# net-stepper2.net
KiCad netlist of a schematic drawn in EAGLE
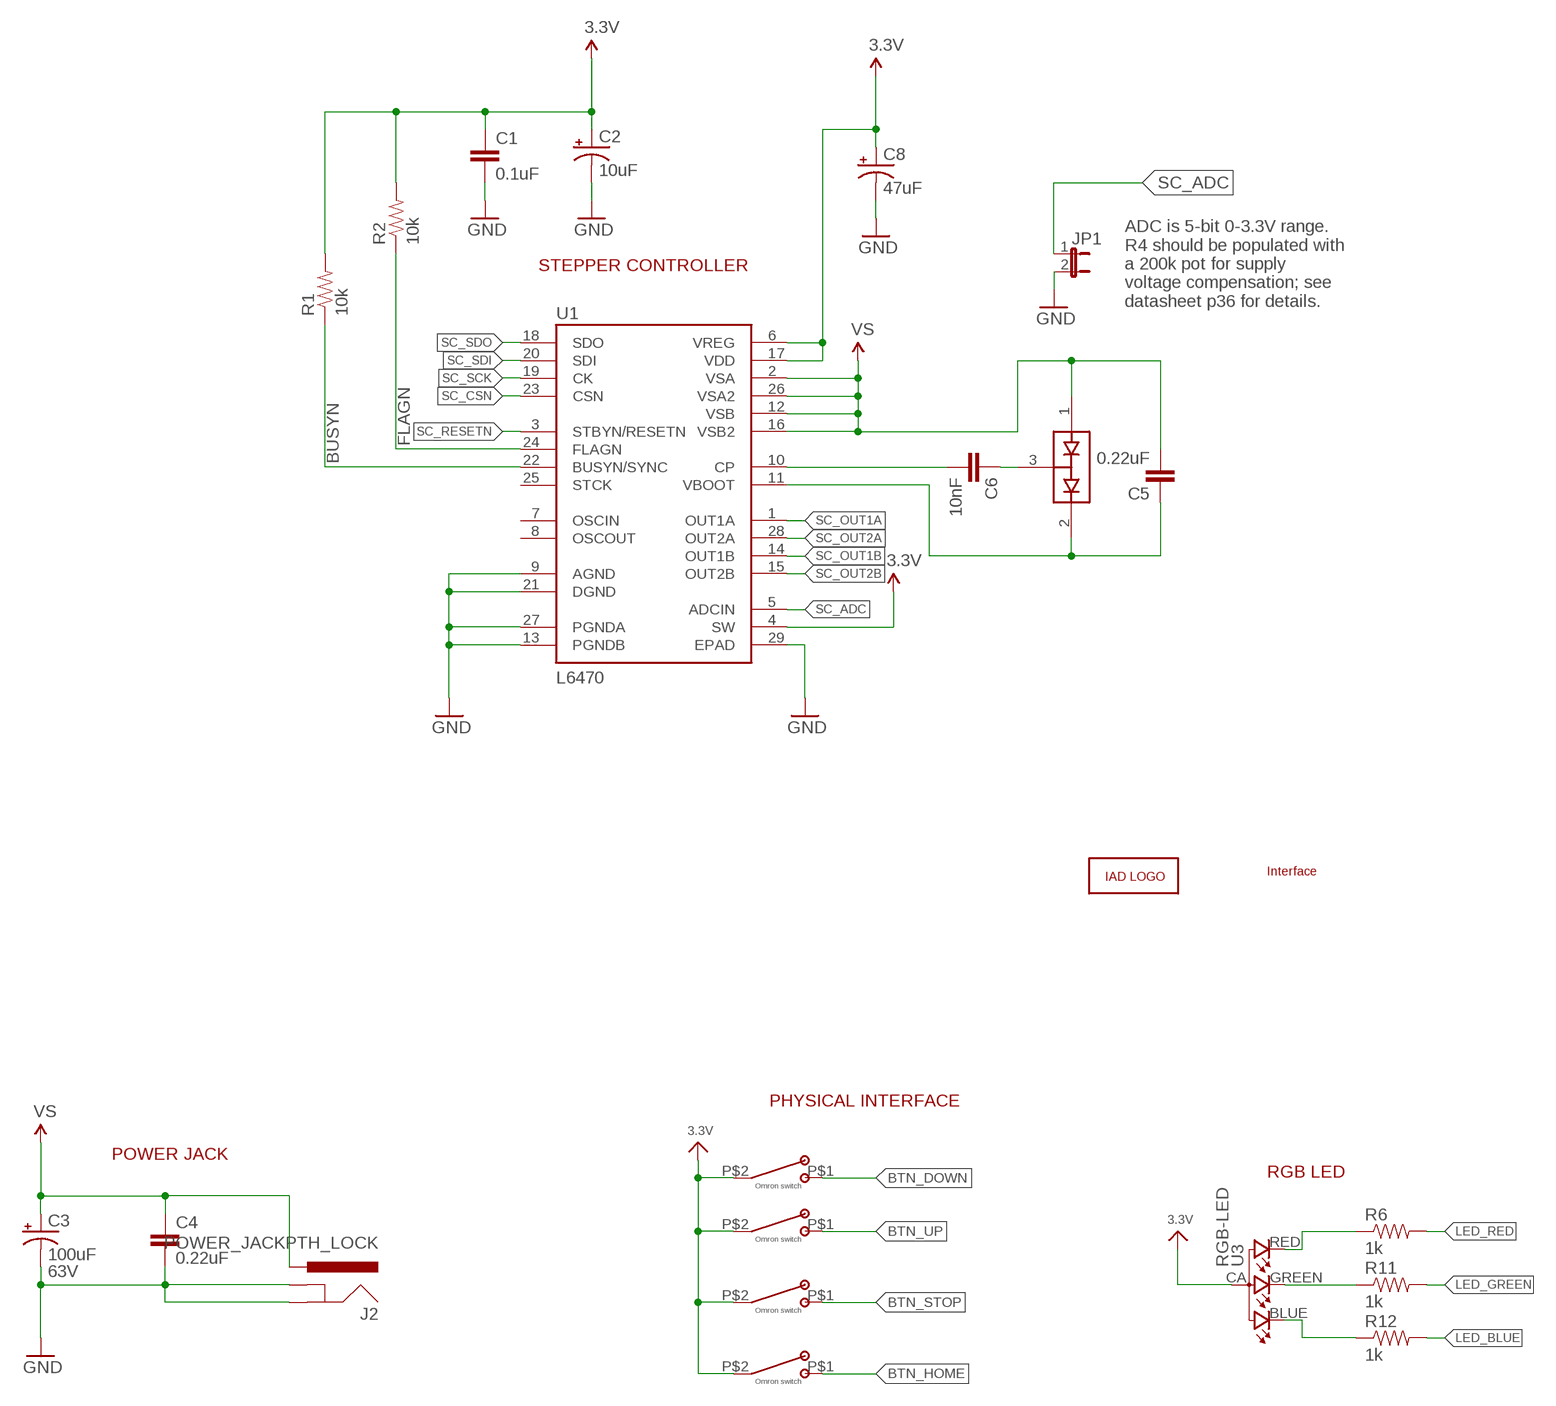
[diagram p0: schematic, sheet 1, part 1 of 2]
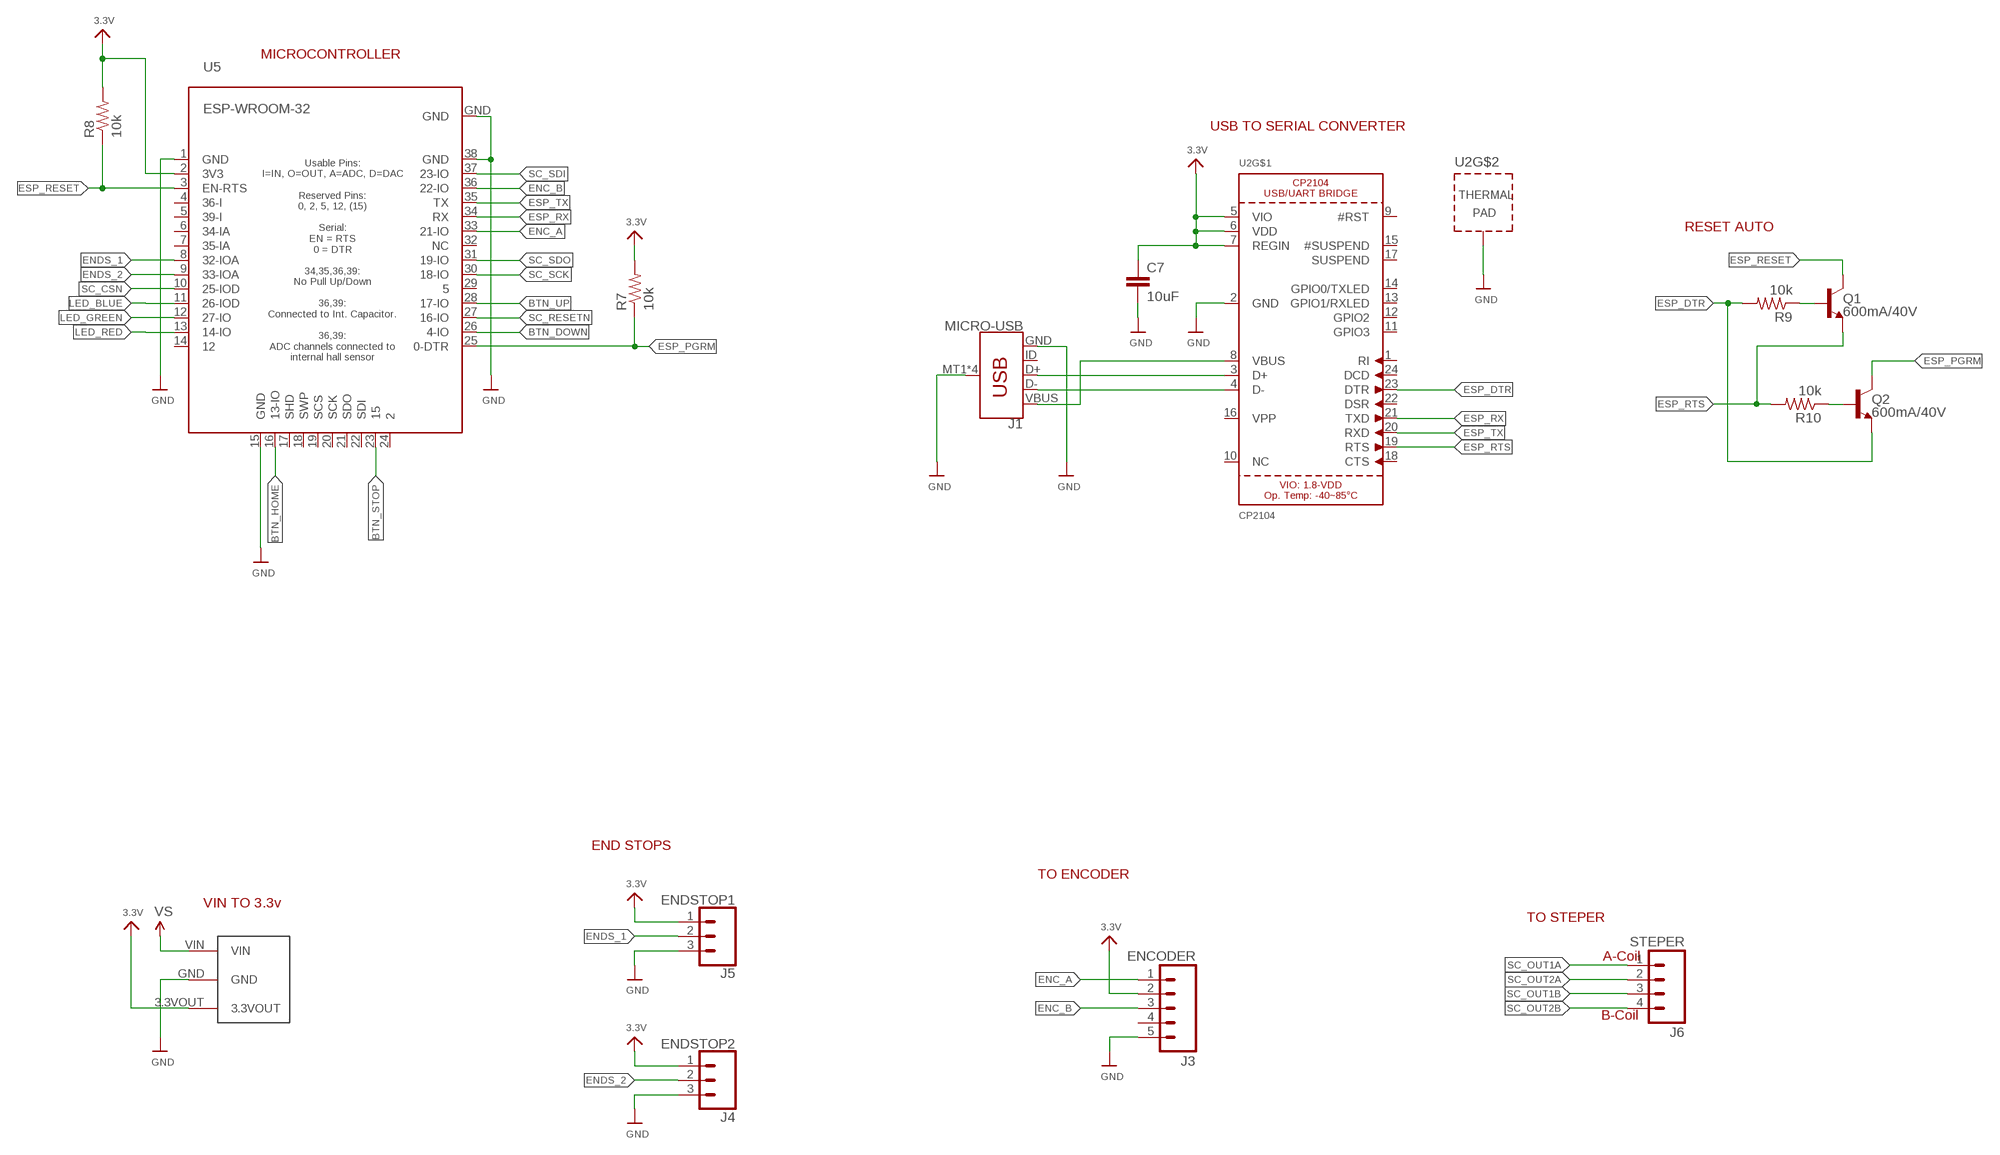
[diagram p1: schematic, sheet 1, part 2 of 2]

(export (version "E")
  (design (tool "Eeschema 10.0.6"))
  (components
    (comp (ref "A1")
      (value "ZHDK_LOGO_METAL")
      (footprint "eagle-import:ZHDK_LOGO")
      (libsource (lib "eagle-import") (part "ZHDK_LOGO_METAL"))
    )
    (comp (ref "A2")
      (value "INTERFACE_NETSTEPPER")
      (footprint "eagle-import:INTERFACE_NETSTEPPER")
      (libsource (lib "eagle-import") (part "INTERFACE_NETSTEPPER"))
    )
    (comp (ref "C1")
      (value "0.1uF")
      (footprint "eagle-import:0603-CAP")
      (libsource (lib "eagle-import") (part "CAP0603-CAP"))
    )
    (comp (ref "C2")
      (value "10uF")
      (footprint "eagle-import:EIA3216")
      (libsource (lib "eagle-import") (part "10UF-TANT"))
    )
    (comp (ref "C3")
      (value "100uF")
      (footprint "eagle-import:NIC_10X10.5_CAP")
      (libsource (lib "eagle-import") (part "100UF-63V-20%(ELECT)"))
    )
    (comp (ref "C4")
      (value "0.22uF")
      (footprint "eagle-import:0603-CAP")
      (libsource (lib "eagle-import") (part "CAP0603-CAP"))
    )
    (comp (ref "C5")
      (value "0.22uF")
      (footprint "eagle-import:0603-CAP")
      (libsource (lib "eagle-import") (part "CAP0603-CAP"))
    )
    (comp (ref "C6")
      (value "10nF")
      (footprint "eagle-import:0603-CAP")
      (libsource (lib "eagle-import") (part "10NF/10000PF-50V-10%(0603)"))
    )
    (comp (ref "C7")
      (value "10uF")
      (footprint "eagle-import:0603")
      (libsource (lib "eagle-import") (part "10UF-0603-6.3V-20%"))
    )
    (comp (ref "C8")
      (value "47uF")
      (footprint "eagle-import:EIA3528")
      (libsource (lib "eagle-import") (part "47UF-TANT"))
    )
    (comp (ref "D1")
      (value "BAV99")
      (footprint "eagle-import:SOT23-3@1")
      (libsource (lib "eagle-import") (part "BAV99"))
    )
    (comp (ref "J1")
      (value "MICRO-USB")
      (footprint "eagle-import:USB-MICROB")
      (libsource (lib "eagle-import") (part "USB_MICRO-B_SMT"))
    )
    (comp (ref "J2")
      (value "POWER_JACKPTH_LOCK")
      (footprint "eagle-import:POWER_JACK_PTH_LOCK")
      (libsource (lib "eagle-import") (part "POWER_JACKPTH_LOCK"))
    )
    (comp (ref "J3")
      (value "ENCODER")
      (footprint "eagle-import:1X05")
      (libsource (lib "eagle-import") (part "M05PTH"))
    )
    (comp (ref "J4")
      (value "ENDSTOP2")
      (footprint "eagle-import:1X03")
      (libsource (lib "eagle-import") (part "CONN_03"))
    )
    (comp (ref "J5")
      (value "ENDSTOP1")
      (footprint "eagle-import:1X03")
      (libsource (lib "eagle-import") (part "CONN_03"))
    )
    (comp (ref "J6")
      (value "STEPER")
      (footprint "eagle-import:1X04_LOCK_LONGPADS")
      (libsource (lib "eagle-import") (part "M04LOCK_LONGPADS"))
    )
    (comp (ref "JP1")
      (value "JUMPER-2SMD-NC")
      (footprint "eagle-import:SJ_2S")
      (libsource (lib "eagle-import") (part "JUMPER-2SMD-NC"))
    )
    (comp (ref "Q1")
      (value "600mA/40V")
      (footprint "eagle-import:SOT23-3")
      (libsource (lib "eagle-import") (part "TRANS_NPN-MMBT2222AL"))
    )
    (comp (ref "Q2")
      (value "600mA/40V")
      (footprint "eagle-import:SOT23-3")
      (libsource (lib "eagle-import") (part "TRANS_NPN-MMBT2222AL"))
    )
    (comp (ref "R1")
      (value "10k")
      (footprint "eagle-import:0603-RES")
      (libsource (lib "eagle-import") (part "RESISTOR0603-RES"))
    )
    (comp (ref "R2")
      (value "10k")
      (footprint "eagle-import:0603-RES")
      (libsource (lib "eagle-import") (part "RESISTOR0603-RES"))
    )
    (comp (ref "R6")
      (value "1k")
      (footprint "eagle-import:0603-RES")
      (libsource (lib "eagle-import") (part "RESISTOR0603-RES"))
    )
    (comp (ref "R7")
      (value "10k")
      (footprint "eagle-import:0603-RES")
      (libsource (lib "eagle-import") (part "RESISTOR0603-RES"))
    )
    (comp (ref "R8")
      (value "10k")
      (footprint "eagle-import:0603-RES")
      (libsource (lib "eagle-import") (part "RESISTOR0603-RES"))
    )
    (comp (ref "R9")
      (value "10k")
      (footprint "eagle-import:0603-RES")
      (libsource (lib "eagle-import") (part "RESISTOR0603-RES"))
    )
    (comp (ref "R10")
      (value "10k")
      (footprint "eagle-import:0603-RES")
      (libsource (lib "eagle-import") (part "RESISTOR0603-RES"))
    )
    (comp (ref "R11")
      (value "1k")
      (footprint "eagle-import:0603-RES")
      (libsource (lib "eagle-import") (part "RESISTOR0603-RES"))
    )
    (comp (ref "R12")
      (value "1k")
      (footprint "eagle-import:0603-RES")
      (libsource (lib "eagle-import") (part "RESISTOR0603-RES"))
    )
    (comp (ref "S1")
      (value "B3AL-1002P-MS")
      (footprint "eagle-import:B3AL-1002P-MS")
      (libsource (lib "eagle-import") (part "B3AL-1002P-MS"))
    )
    (comp (ref "S2")
      (value "B3AL-1002P-MS")
      (footprint "eagle-import:B3AL-1002P-MS")
      (libsource (lib "eagle-import") (part "B3AL-1002P-MS"))
    )
    (comp (ref "S3")
      (value "B3AL-1002P-MS")
      (footprint "eagle-import:B3AL-1002P-MS")
      (libsource (lib "eagle-import") (part "B3AL-1002P-MS"))
    )
    (comp (ref "S4")
      (value "B3AL-1002P-MS")
      (footprint "eagle-import:B3AL-1002P-MS")
      (libsource (lib "eagle-import") (part "B3AL-1002P-MS"))
    )
    (comp (ref "U1")
      (value "L6470")
      (footprint "eagle-import:HTSSOP28")
      (libsource (lib "eagle-import") (part "L6470"))
    )
    (comp (ref "U2")
      (value "CP2104")
      (footprint "eagle-import:QFN24_4MM_SMSC")
      (libsource (lib "eagle-import") (part "CP2104"))
    )
    (comp (ref "U3")
      (value "RGB-LED")
      (footprint "eagle-import:PLCC4-2MM-RGB")
      (libsource (lib "eagle-import") (part "RGB-LED-CLMVB-FKARGB"))
    )
    (comp (ref "U4")
      (value "TRACO12433")
      (footprint "eagle-import:TRACO12433")
      (libsource (lib "eagle-import") (part "TRACO12433"))
    )
    (comp (ref "U5")
      (value "ESP-WROOM-32")
      (footprint "eagle-import:ESP-WROOM-32")
      (libsource (lib "eagle-import") (part "ESP-WROOM-32"))
    )
  )
  (nets
    (net (code "1") (name "/BUSYN") (class "Default")
      (node (ref "R1") (pin "1") (pinfunction "1_1") (pintype "passive"))
      (node (ref "U1") (pin "22") (pinfunction "BUSYN/SYNC_22") (pintype "bidirectional"))
    )
    (net (code "2") (name "/FLAGN") (class "Default")
      (node (ref "R2") (pin "1") (pinfunction "1_1") (pintype "passive"))
      (node (ref "U1") (pin "24") (pinfunction "FLAGN_24") (pintype "bidirectional"))
    )
    (net (code "3") (name "3.3V") (class "Default")
      (node (ref "C1") (pin "1") (pinfunction "1_1") (pintype "passive"))
      (node (ref "C2") (pin "A") (pinfunction "+_A") (pintype "passive"))
      (node (ref "C7") (pin "1") (pinfunction "1_1") (pintype "passive"))
      (node (ref "C8") (pin "A") (pinfunction "+_A") (pintype "passive"))
      (node (ref "J3") (pin "2") (pinfunction "2_2") (pintype "passive"))
      (node (ref "J4") (pin "1") (pinfunction "1_1") (pintype "passive"))
      (node (ref "J5") (pin "1") (pinfunction "1_1") (pintype "passive"))
      (node (ref "R1") (pin "2") (pinfunction "2_2") (pintype "passive"))
      (node (ref "R2") (pin "2") (pinfunction "2_2") (pintype "passive"))
      (node (ref "R7") (pin "2") (pinfunction "2_2") (pintype "passive"))
      (node (ref "R8") (pin "2") (pinfunction "2_2") (pintype "passive"))
      (node (ref "S1") (pin "P$2") (pinfunction "P$2_P$2") (pintype "bidirectional"))
      (node (ref "S2") (pin "P$2") (pinfunction "P$2_P$2") (pintype "bidirectional"))
      (node (ref "S3") (pin "P$2") (pinfunction "P$2_P$2") (pintype "bidirectional"))
      (node (ref "S4") (pin "P$2") (pinfunction "P$2_P$2") (pintype "bidirectional"))
      (node (ref "U1") (pin "17") (pinfunction "VDD_17") (pintype "bidirectional"))
      (node (ref "U1") (pin "4") (pinfunction "SW_4") (pintype "bidirectional"))
      (node (ref "U1") (pin "6") (pinfunction "VREG_6") (pintype "bidirectional"))
      (node (ref "U2") (pin "5") (pinfunction "VIO_5") (pintype "power_in"))
      (node (ref "U2") (pin "6") (pinfunction "VDD_6") (pintype "power_in"))
      (node (ref "U2") (pin "7") (pinfunction "REGIN_7") (pintype "power_in"))
      (node (ref "U3") (pin "CA") (pinfunction "1_CA") (pintype "passive"))
      (node (ref "U4") (pin "3.3VOUT") (pinfunction "3.3VOUT_3.3VOUT") (pintype "bidirectional"))
      (node (ref "U5") (pin "2") (pinfunction "3V3_2") (pintype "bidirectional"))
    )
    (net (code "4") (name "BTN_DOWN") (class "Default")
      (node (ref "S1") (pin "P$1") (pinfunction "P$1_P$1") (pintype "bidirectional"))
      (node (ref "U5") (pin "26") (pinfunction "4-IO_26") (pintype "bidirectional"))
    )
    (net (code "5") (name "BTN_HOME") (class "Default")
      (node (ref "S4") (pin "P$1") (pinfunction "P$1_P$1") (pintype "bidirectional"))
      (node (ref "U5") (pin "16") (pinfunction "13-IO_16") (pintype "bidirectional"))
    )
    (net (code "6") (name "BTN_STOP") (class "Default")
      (node (ref "S3") (pin "P$1") (pinfunction "P$1_P$1") (pintype "bidirectional"))
      (node (ref "U5") (pin "23") (pinfunction "15_23") (pintype "bidirectional"))
    )
    (net (code "7") (name "BTN_UP") (class "Default")
      (node (ref "S2") (pin "P$1") (pinfunction "P$1_P$1") (pintype "bidirectional"))
      (node (ref "U5") (pin "28") (pinfunction "17-IO_28") (pintype "bidirectional"))
    )
    (net (code "8") (name "ENC_A") (class "Default")
      (node (ref "J3") (pin "1") (pinfunction "1_1") (pintype "passive"))
      (node (ref "U5") (pin "33") (pinfunction "21-IO_33") (pintype "bidirectional"))
    )
    (net (code "9") (name "ENC_B") (class "Default")
      (node (ref "J3") (pin "3") (pinfunction "3_3") (pintype "passive"))
      (node (ref "U5") (pin "36") (pinfunction "22-IO_36") (pintype "bidirectional"))
    )
    (net (code "10") (name "ENDS_1") (class "Default")
      (node (ref "J5") (pin "2") (pinfunction "2_2") (pintype "passive"))
      (node (ref "U5") (pin "8") (pinfunction "32-IOA_8") (pintype "bidirectional"))
    )
    (net (code "11") (name "ENDS_2") (class "Default")
      (node (ref "J4") (pin "2") (pinfunction "2_2") (pintype "passive"))
      (node (ref "U5") (pin "9") (pinfunction "33-IOA_9") (pintype "bidirectional"))
    )
    (net (code "12") (name "ESP_DTR") (class "Default")
      (node (ref "Q2") (pin "2") (pinfunction "E_2") (pintype "passive"))
      (node (ref "R9") (pin "2") (pinfunction "2_2") (pintype "passive"))
      (node (ref "U2") (pin "23") (pinfunction "DTR_23") (pintype "output"))
    )
    (net (code "13") (name "ESP_PGRM") (class "Default")
      (node (ref "Q2") (pin "3") (pinfunction "C_3") (pintype "passive"))
      (node (ref "R7") (pin "1") (pinfunction "1_1") (pintype "passive"))
      (node (ref "U5") (pin "25") (pinfunction "0-DTR_25") (pintype "bidirectional"))
    )
    (net (code "14") (name "ESP_RESET") (class "Default")
      (node (ref "Q1") (pin "3") (pinfunction "C_3") (pintype "passive"))
      (node (ref "R8") (pin "1") (pinfunction "1_1") (pintype "passive"))
      (node (ref "U5") (pin "3") (pinfunction "EN-RTS_3") (pintype "bidirectional"))
    )
    (net (code "15") (name "ESP_RTS") (class "Default")
      (node (ref "Q1") (pin "2") (pinfunction "E_2") (pintype "passive"))
      (node (ref "R10") (pin "2") (pinfunction "2_2") (pintype "passive"))
      (node (ref "U2") (pin "19") (pinfunction "RTS_19") (pintype "output"))
    )
    (net (code "16") (name "ESP_RX") (class "Default")
      (node (ref "U2") (pin "21") (pinfunction "TXD_21") (pintype "output"))
      (node (ref "U5") (pin "34") (pinfunction "RX_34") (pintype "bidirectional"))
    )
    (net (code "17") (name "ESP_TX") (class "Default")
      (node (ref "U2") (pin "20") (pinfunction "RXD_20") (pintype "input"))
      (node (ref "U5") (pin "35") (pinfunction "TX_35") (pintype "bidirectional"))
    )
    (net (code "18") (name "GND") (class "Default")
      (node (ref "C1") (pin "2") (pinfunction "2_2") (pintype "passive"))
      (node (ref "C2") (pin "C") (pinfunction "-_C") (pintype "passive"))
      (node (ref "C3") (pin "-") (pinfunction "-_-") (pintype "passive"))
      (node (ref "C4") (pin "2") (pinfunction "2_2") (pintype "passive"))
      (node (ref "C7") (pin "2") (pinfunction "2_2") (pintype "passive"))
      (node (ref "C8") (pin "C") (pinfunction "-_C") (pintype "passive"))
      (node (ref "J1") (pin "GND") (pinfunction "GND_GND") (pintype "power_in"))
      (node (ref "J1") (pin "MT1") (pinfunction "SHIELD_MT1") (pintype "bidirectional"))
      (node (ref "J1") (pin "MT2") (pinfunction "SHIELD_MT2") (pintype "bidirectional"))
      (node (ref "J1") (pin "P$1") (pinfunction "SHIELD_P$1") (pintype "bidirectional"))
      (node (ref "J1") (pin "P$2") (pinfunction "SHIELD_P$2") (pintype "bidirectional"))
      (node (ref "J2") (pin "GND") (pinfunction "GND_GND") (pintype "bidirectional"))
      (node (ref "J2") (pin "GNDBREAK") (pinfunction "GNDBREAK_GNDBREAK") (pintype "bidirectional"))
      (node (ref "J3") (pin "5") (pinfunction "5_5") (pintype "passive"))
      (node (ref "J4") (pin "3") (pinfunction "3_3") (pintype "passive"))
      (node (ref "J5") (pin "3") (pinfunction "3_3") (pintype "passive"))
      (node (ref "JP1") (pin "2") (pinfunction "2_2") (pintype "passive"))
      (node (ref "U1") (pin "13") (pinfunction "PGNDB_13") (pintype "bidirectional"))
      (node (ref "U1") (pin "21") (pinfunction "DGND_21") (pintype "bidirectional"))
      (node (ref "U1") (pin "27") (pinfunction "PGNDA_27") (pintype "bidirectional"))
      (node (ref "U1") (pin "29") (pinfunction "EPAD_29") (pintype "bidirectional"))
      (node (ref "U1") (pin "9") (pinfunction "AGND_9") (pintype "bidirectional"))
      (node (ref "U2") (pin "2") (pinfunction "GND_2") (pintype "power_in"))
      (node (ref "U2") (pin "THERM") (pinfunction "TP_THERM") (pintype "power_in"))
      (node (ref "U4") (pin "GND") (pinfunction "GND_GND") (pintype "bidirectional"))
      (node (ref "U5") (pin "1") (pinfunction "GND_1") (pintype "bidirectional"))
      (node (ref "U5") (pin "15") (pinfunction "GND_15") (pintype "bidirectional"))
      (node (ref "U5") (pin "38") (pinfunction "GND_38") (pintype "bidirectional"))
      (node (ref "U5") (pin "GND") (pinfunction "GND_GND") (pintype "bidirectional"))
    )
    (net (code "19") (name "LED_BLUE") (class "Default")
      (node (ref "R12") (pin "2") (pinfunction "2_2") (pintype "passive"))
      (node (ref "U5") (pin "11") (pinfunction "26-IOD_11") (pintype "bidirectional"))
    )
    (net (code "20") (name "LED_GREEN") (class "Default")
      (node (ref "R11") (pin "2") (pinfunction "2_2") (pintype "passive"))
      (node (ref "U5") (pin "12") (pinfunction "27-IO_12") (pintype "bidirectional"))
    )
    (net (code "21") (name "LED_RED") (class "Default")
      (node (ref "R6") (pin "2") (pinfunction "2_2") (pintype "passive"))
      (node (ref "U5") (pin "13") (pinfunction "14-IO_13") (pintype "bidirectional"))
    )
    (net (code "22") (name "Net-(D1-C2)") (class "Default")
      (node (ref "C5") (pin "1") (pinfunction "1_1") (pintype "passive"))
      (node (ref "D1") (pin "2") (pinfunction "C2_2") (pintype "bidirectional"))
      (node (ref "U1") (pin "11") (pinfunction "VBOOT_11") (pintype "bidirectional"))
    )
    (net (code "23") (name "Net-(D1-COM)") (class "Default")
      (node (ref "C6") (pin "1") (pinfunction "1_1") (pintype "passive"))
      (node (ref "D1") (pin "3") (pinfunction "COM_3") (pintype "bidirectional"))
    )
    (net (code "24") (name "Net-(Q1-B)") (class "Default")
      (node (ref "Q1") (pin "1") (pinfunction "B_1") (pintype "passive"))
      (node (ref "R9") (pin "1") (pinfunction "1_1") (pintype "passive"))
    )
    (net (code "25") (name "Net-(Q2-B)") (class "Default")
      (node (ref "Q2") (pin "1") (pinfunction "B_1") (pintype "passive"))
      (node (ref "R10") (pin "1") (pinfunction "1_1") (pintype "passive"))
    )
    (net (code "26") (name "Net-(U1-CP)") (class "Default")
      (node (ref "C6") (pin "2") (pinfunction "2_2") (pintype "passive"))
      (node (ref "U1") (pin "10") (pinfunction "CP_10") (pintype "bidirectional"))
    )
    (net (code "27") (name "Net-(U2A-D+)") (class "Default")
      (node (ref "J1") (pin "D+") (pinfunction "D+_D+") (pintype "bidirectional"))
      (node (ref "U2") (pin "3") (pinfunction "D+_3") (pintype "bidirectional"))
    )
    (net (code "28") (name "Net-(U2A-D-)") (class "Default")
      (node (ref "J1") (pin "D-") (pinfunction "D-_D-") (pintype "bidirectional"))
      (node (ref "U2") (pin "4") (pinfunction "D-_4") (pintype "bidirectional"))
    )
    (net (code "29") (name "Net-(U2A-VBUS)") (class "Default")
      (node (ref "J1") (pin "VBUS") (pinfunction "VBUS_VBUS") (pintype "power_in"))
      (node (ref "U2") (pin "8") (pinfunction "VBUS_8") (pintype "power_in"))
    )
    (net (code "30") (name "Net-(U3-2)") (class "Default")
      (node (ref "R12") (pin "1") (pinfunction "1_1") (pintype "passive"))
      (node (ref "U3") (pin "BLUE") (pinfunction "2_BLUE") (pintype "passive"))
    )
    (net (code "31") (name "Net-(U3-3)") (class "Default")
      (node (ref "R11") (pin "1") (pinfunction "1_1") (pintype "passive"))
      (node (ref "U3") (pin "GREEN") (pinfunction "3_GREEN") (pintype "passive"))
    )
    (net (code "32") (name "Net-(U3-4)") (class "Default")
      (node (ref "R6") (pin "1") (pinfunction "1_1") (pintype "passive"))
      (node (ref "U3") (pin "RED") (pinfunction "4_RED") (pintype "passive"))
    )
    (net (code "33") (name "SC_ADC") (class "Default")
      (node (ref "JP1") (pin "1") (pinfunction "1_1") (pintype "passive"))
      (node (ref "U1") (pin "5") (pinfunction "ADCIN_5") (pintype "bidirectional"))
    )
    (net (code "34") (name "SC_CSN") (class "Default")
      (node (ref "U1") (pin "23") (pinfunction "CSN_23") (pintype "bidirectional"))
      (node (ref "U5") (pin "10") (pinfunction "25-IOD_10") (pintype "bidirectional"))
    )
    (net (code "35") (name "SC_OUT1A") (class "Default")
      (node (ref "J6") (pin "1") (pinfunction "1_1") (pintype "passive"))
      (node (ref "U1") (pin "1") (pinfunction "OUT1A_1") (pintype "bidirectional"))
    )
    (net (code "36") (name "SC_OUT1B") (class "Default")
      (node (ref "J6") (pin "3") (pinfunction "3_3") (pintype "passive"))
      (node (ref "U1") (pin "14") (pinfunction "OUT1B_14") (pintype "bidirectional"))
    )
    (net (code "37") (name "SC_OUT2A") (class "Default")
      (node (ref "J6") (pin "2") (pinfunction "2_2") (pintype "passive"))
      (node (ref "U1") (pin "28") (pinfunction "OUT2A_28") (pintype "bidirectional"))
    )
    (net (code "38") (name "SC_OUT2B") (class "Default")
      (node (ref "J6") (pin "4") (pinfunction "4_4") (pintype "passive"))
      (node (ref "U1") (pin "15") (pinfunction "OUT2B_15") (pintype "bidirectional"))
    )
    (net (code "39") (name "SC_RESETN") (class "Default")
      (node (ref "U1") (pin "3") (pinfunction "STBYN/RESETN_3") (pintype "bidirectional"))
      (node (ref "U5") (pin "27") (pinfunction "16-IO_27") (pintype "bidirectional"))
    )
    (net (code "40") (name "SC_SCK") (class "Default")
      (node (ref "U1") (pin "19") (pinfunction "CK_19") (pintype "bidirectional"))
      (node (ref "U5") (pin "30") (pinfunction "18-IO_30") (pintype "bidirectional"))
    )
    (net (code "41") (name "SC_SDI") (class "Default")
      (node (ref "U1") (pin "20") (pinfunction "SDI_20") (pintype "bidirectional"))
      (node (ref "U5") (pin "37") (pinfunction "23-IO_37") (pintype "bidirectional"))
    )
    (net (code "42") (name "SC_SDO") (class "Default")
      (node (ref "U1") (pin "18") (pinfunction "SDO_18") (pintype "bidirectional"))
      (node (ref "U5") (pin "31") (pinfunction "19-IO_31") (pintype "bidirectional"))
    )
    (net (code "43") (name "VS") (class "Default")
      (node (ref "C3") (pin "+") (pinfunction "+_+") (pintype "passive"))
      (node (ref "C4") (pin "1") (pinfunction "1_1") (pintype "passive"))
      (node (ref "C5") (pin "2") (pinfunction "2_2") (pintype "passive"))
      (node (ref "D1") (pin "1") (pinfunction "A1_1") (pintype "bidirectional"))
      (node (ref "J2") (pin "PWR") (pinfunction "PWR_PWR") (pintype "bidirectional"))
      (node (ref "U1") (pin "12") (pinfunction "VSB_12") (pintype "bidirectional"))
      (node (ref "U1") (pin "16") (pinfunction "VSB2_16") (pintype "bidirectional"))
      (node (ref "U1") (pin "2") (pinfunction "VSA_2") (pintype "bidirectional"))
      (node (ref "U1") (pin "26") (pinfunction "VSA2_26") (pintype "bidirectional"))
      (node (ref "U4") (pin "VIN") (pinfunction "VIN_VIN") (pintype "bidirectional"))
    )
    (net (code "44") (name "unconnected-(J1-PadID)") (class "Default")
      (node (ref "J1") (pin "ID") (pinfunction "ID_ID") (pintype "bidirectional"))
    )
    (net (code "45") (name "unconnected-(J3-Pad4)") (class "Default")
      (node (ref "J3") (pin "4") (pinfunction "4_4") (pintype "passive"))
    )
    (net (code "46") (name "unconnected-(U1-OSCIN-Pad7)") (class "Default")
      (node (ref "U1") (pin "7") (pinfunction "OSCIN_7") (pintype "bidirectional"))
    )
    (net (code "47") (name "unconnected-(U1-OSCOUT-Pad8)") (class "Default")
      (node (ref "U1") (pin "8") (pinfunction "OSCOUT_8") (pintype "bidirectional"))
    )
    (net (code "48") (name "unconnected-(U1-STCK-Pad25)") (class "Default")
      (node (ref "U1") (pin "25") (pinfunction "STCK_25") (pintype "bidirectional"))
    )
    (net (code "49") (name "unconnected-(U2A-#RST-Pad9)") (class "Default")
      (node (ref "U2") (pin "9") (pinfunction "#RST_9") (pintype "bidirectional"))
    )
    (net (code "50") (name "unconnected-(U2A-#SUSPEND-Pad15)") (class "Default")
      (node (ref "U2") (pin "15") (pinfunction "#SUSPEND_15") (pintype "output"))
    )
    (net (code "51") (name "unconnected-(U2A-CTS-Pad18)") (class "Default")
      (node (ref "U2") (pin "18") (pinfunction "CTS_18") (pintype "input"))
    )
    (net (code "52") (name "unconnected-(U2A-DCD-Pad24)") (class "Default")
      (node (ref "U2") (pin "24") (pinfunction "DCD_24") (pintype "input"))
    )
    (net (code "53") (name "unconnected-(U2A-DSR-Pad22)") (class "Default")
      (node (ref "U2") (pin "22") (pinfunction "DSR_22") (pintype "input"))
    )
    (net (code "54") (name "unconnected-(U2A-GPIO0{slash}TXLED-Pad14)") (class "Default")
      (node (ref "U2") (pin "14") (pinfunction "GPIO0/TXLED_14") (pintype "bidirectional"))
    )
    (net (code "55") (name "unconnected-(U2A-GPIO1{slash}RXLED-Pad13)") (class "Default")
      (node (ref "U2") (pin "13") (pinfunction "GPIO1/RXLED_13") (pintype "bidirectional"))
    )
    (net (code "56") (name "unconnected-(U2A-GPIO2-Pad12)") (class "Default")
      (node (ref "U2") (pin "12") (pinfunction "GPIO2_12") (pintype "bidirectional"))
    )
    (net (code "57") (name "unconnected-(U2A-GPIO3-Pad11)") (class "Default")
      (node (ref "U2") (pin "11") (pinfunction "GPIO3_11") (pintype "bidirectional"))
    )
    (net (code "58") (name "unconnected-(U2A-NC-Pad10)") (class "Default")
      (node (ref "U2") (pin "10") (pinfunction "NC_10") (pintype "no_connect"))
    )
    (net (code "59") (name "unconnected-(U2A-RI-Pad1)") (class "Default")
      (node (ref "U2") (pin "1") (pinfunction "RI_1") (pintype "input"))
    )
    (net (code "60") (name "unconnected-(U2A-SUSPEND-Pad17)") (class "Default")
      (node (ref "U2") (pin "17") (pinfunction "SUSPEND_17") (pintype "output"))
    )
    (net (code "61") (name "unconnected-(U2A-VPP-Pad16)") (class "Default")
      (node (ref "U2") (pin "16") (pinfunction "VPP_16") (pintype "bidirectional"))
    )
    (net (code "62") (name "unconnected-(U5-2-Pad24)") (class "Default")
      (node (ref "U5") (pin "24") (pinfunction "2_24") (pintype "bidirectional"))
    )
    (net (code "63") (name "unconnected-(U5-5-Pad29)") (class "Default")
      (node (ref "U5") (pin "29") (pinfunction "5_29") (pintype "bidirectional"))
    )
    (net (code "64") (name "unconnected-(U5-12-Pad14)") (class "Default")
      (node (ref "U5") (pin "14") (pinfunction "12_14") (pintype "bidirectional"))
    )
    (net (code "65") (name "unconnected-(U5-34-IA-Pad6)") (class "Default")
      (node (ref "U5") (pin "6") (pinfunction "34-IA_6") (pintype "bidirectional"))
    )
    (net (code "66") (name "unconnected-(U5-35-IA-Pad7)") (class "Default")
      (node (ref "U5") (pin "7") (pinfunction "35-IA_7") (pintype "bidirectional"))
    )
    (net (code "67") (name "unconnected-(U5-36-I-Pad4)") (class "Default")
      (node (ref "U5") (pin "4") (pinfunction "36-I_4") (pintype "bidirectional"))
    )
    (net (code "68") (name "unconnected-(U5-39-I-Pad5)") (class "Default")
      (node (ref "U5") (pin "5") (pinfunction "39-I_5") (pintype "bidirectional"))
    )
    (net (code "69") (name "unconnected-(U5-NC-Pad32)") (class "Default")
      (node (ref "U5") (pin "32") (pinfunction "NC_32") (pintype "bidirectional"))
    )
    (net (code "70") (name "unconnected-(U5-SCK-Pad20)") (class "Default")
      (node (ref "U5") (pin "20") (pinfunction "SCK_20") (pintype "bidirectional"))
    )
    (net (code "71") (name "unconnected-(U5-SCS-Pad19)") (class "Default")
      (node (ref "U5") (pin "19") (pinfunction "SCS_19") (pintype "bidirectional"))
    )
    (net (code "72") (name "unconnected-(U5-SDI-Pad22)") (class "Default")
      (node (ref "U5") (pin "22") (pinfunction "SDI_22") (pintype "bidirectional"))
    )
    (net (code "73") (name "unconnected-(U5-SDO-Pad21)") (class "Default")
      (node (ref "U5") (pin "21") (pinfunction "SDO_21") (pintype "bidirectional"))
    )
    (net (code "74") (name "unconnected-(U5-SHD-Pad17)") (class "Default")
      (node (ref "U5") (pin "17") (pinfunction "SHD_17") (pintype "bidirectional"))
    )
    (net (code "75") (name "unconnected-(U5-SWP-Pad18)") (class "Default")
      (node (ref "U5") (pin "18") (pinfunction "SWP_18") (pintype "bidirectional"))
    )
  )
)
